# channel.net
KiCad netlist of a schematic drawn in Altium Designer
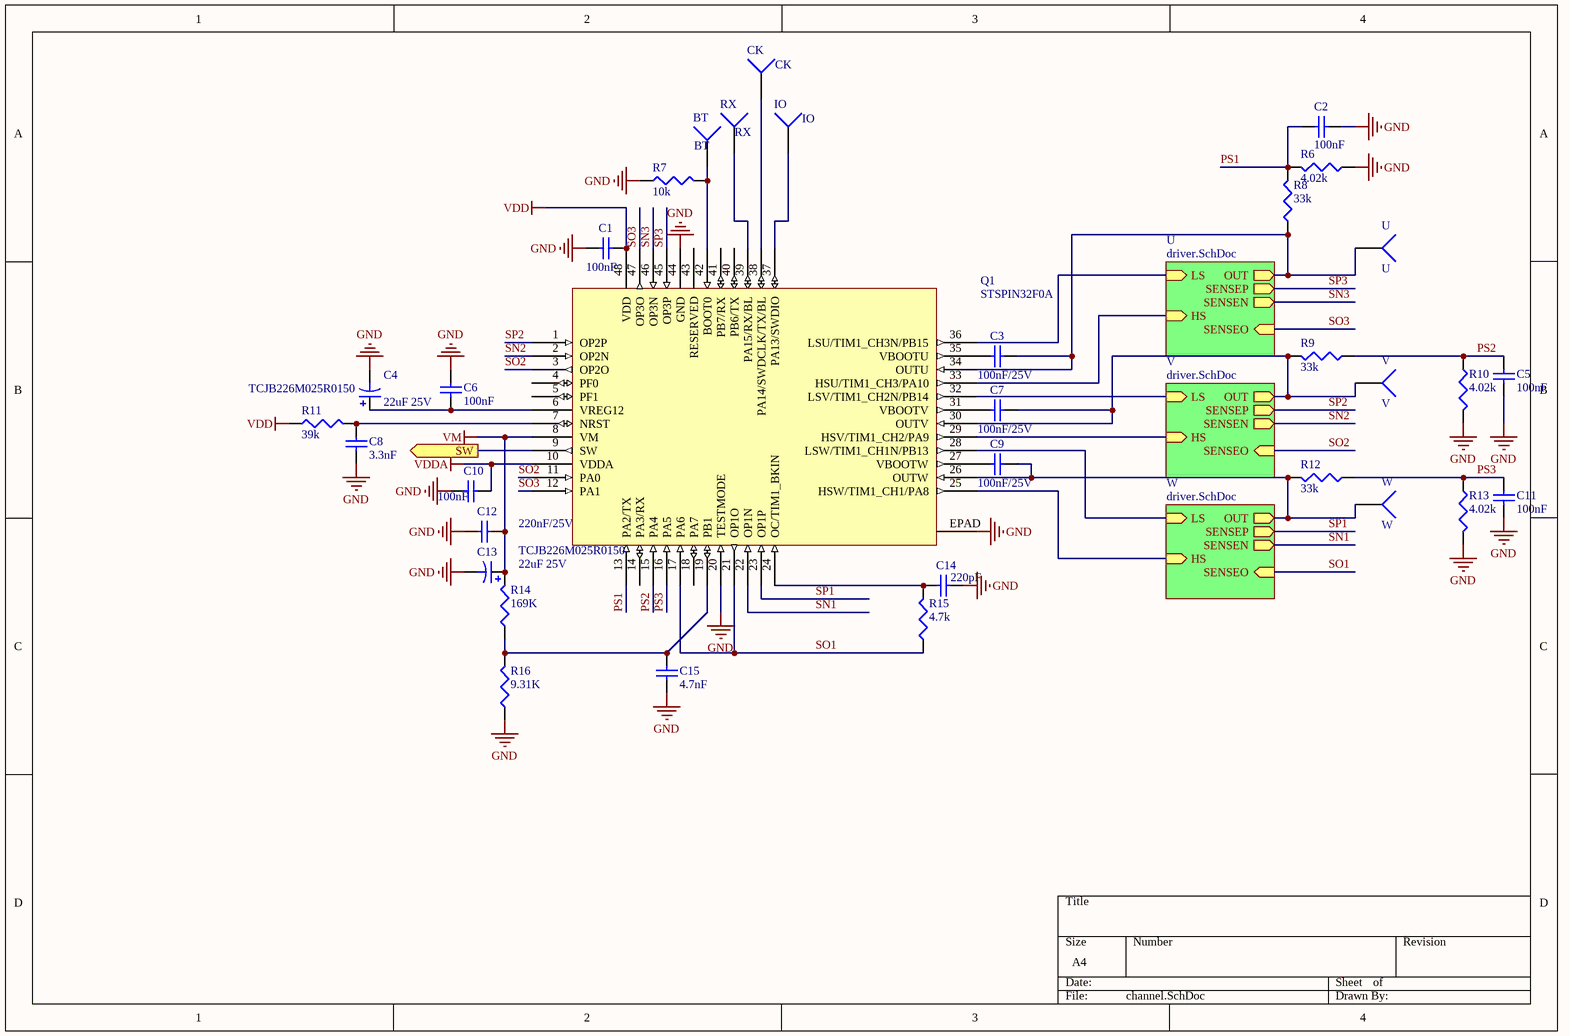
[diagram p0: channel.SchDoc]

(export (version "E")
  (design (tool "Eeschema 10.0.6"))
  (components
    (comp (ref "BT")
      (value "BT")
      (footprint "solder_pin_small")
      (description "Socket")
      (fields (field (name "PUBLISHER") "Altium Limited"))
      (libsource (lib "Miscellaneous Connectors") (part "Socket"))
    )
    (comp (ref "C1")
      (value "100nF")
      (description "Capacitor")
      (fields (field (name "PUBLISHER") "Altium Limited"))
      (libsource (lib "Miscellaneous Devices") (part "Cap"))
    )
    (comp (ref "C2")
      (value "100nF")
      (description "Capacitor")
      (fields (field (name "PUBLISHER") "Altium Limited"))
      (libsource (lib "Miscellaneous Devices") (part "Cap"))
    )
    (comp (ref "C3")
      (value "100nF/25V")
      (description "Capacitor")
      (fields (field (name "PUBLISHER") "Altium Limited"))
      (libsource (lib "Miscellaneous Devices") (part "Cap"))
    )
    (comp (ref "C4")
      (value "TCJB226M025R0150")
      (footprint "my_1210_pol")
      (description "Polarized Capacitor (Surface Mount)")
      (fields (field (name "ALTIUM_VALUE") "22uF 25V") (field (name "PUBLISHER") "Altium Limited"))
      (libsource (lib "Miscellaneous Devices") (part "Cap Pol3"))
    )
    (comp (ref "C5")
      (value "100nF")
      (description "Capacitor")
      (fields (field (name "PUBLISHER") "Altium Limited"))
      (libsource (lib "Miscellaneous Devices") (part "Cap"))
    )
    (comp (ref "C6")
      (value "100nF")
      (description "Capacitor")
      (fields (field (name "PUBLISHER") "Altium Limited"))
      (libsource (lib "Miscellaneous Devices") (part "Cap"))
    )
    (comp (ref "C7")
      (value "100nF/25V")
      (description "Capacitor")
      (fields (field (name "PUBLISHER") "Altium Limited"))
      (libsource (lib "Miscellaneous Devices") (part "Cap"))
    )
    (comp (ref "C8")
      (value "3.3nF")
      (description "Capacitor")
      (fields (field (name "PUBLISHER") "Altium Limited"))
      (libsource (lib "Miscellaneous Devices") (part "Cap"))
    )
    (comp (ref "C9")
      (value "100nF/25V")
      (description "Capacitor")
      (fields (field (name "PUBLISHER") "Altium Limited"))
      (libsource (lib "Miscellaneous Devices") (part "Cap"))
    )
    (comp (ref "C10")
      (value "100nF")
      (description "Capacitor")
      (fields (field (name "PUBLISHER") "Altium Limited"))
      (libsource (lib "Miscellaneous Devices") (part "Cap"))
    )
    (comp (ref "C11")
      (value "100nF")
      (description "Capacitor")
      (fields (field (name "PUBLISHER") "Altium Limited"))
      (libsource (lib "Miscellaneous Devices") (part "Cap"))
    )
    (comp (ref "C12")
      (value "220nF/25V")
      (description "Capacitor")
      (fields (field (name "PUBLISHER") "Altium Limited"))
      (libsource (lib "Miscellaneous Devices") (part "Cap"))
    )
    (comp (ref "C13")
      (value "TCJB226M025R0150")
      (footprint "my_1210_pol")
      (description "Polarized Capacitor (Surface Mount)")
      (fields (field (name "ALTIUM_VALUE") "22uF 25V") (field (name "PUBLISHER") "Altium Limited"))
      (libsource (lib "Miscellaneous Devices") (part "Cap Pol3"))
    )
    (comp (ref "C14")
      (value "220pF")
      (description "Capacitor")
      (fields (field (name "PUBLISHER") "Altium Limited"))
      (libsource (lib "Miscellaneous Devices") (part "Cap"))
    )
    (comp (ref "C15")
      (value "4.7nF")
      (description "Capacitor")
      (fields (field (name "PUBLISHER") "Altium Limited"))
      (libsource (lib "Miscellaneous Devices") (part "Cap"))
    )
    (comp (ref "CK")
      (value "CK")
      (footprint "solder_pin_small")
      (description "Socket")
      (fields (field (name "PUBLISHER") "Altium Limited"))
      (libsource (lib "Miscellaneous Connectors") (part "Socket"))
    )
    (comp (ref "IO")
      (value "IO")
      (footprint "solder_pin_small")
      (description "Socket")
      (fields (field (name "PUBLISHER") "Altium Limited"))
      (libsource (lib "Miscellaneous Connectors") (part "Socket"))
    )
    (comp (ref "Q1")
      (value "STSPIN32F0A")
      (footprint "VFQFPN48")
      (libsource (lib "components") (part "STSPIN32F0A"))
    )
    (comp (ref "R6")
      (value "4.02k")
      (description "Resistor")
      (fields (field (name "PUBLISHER") "Altium Limited"))
      (libsource (lib "Miscellaneous Devices") (part "Res3"))
    )
    (comp (ref "R7")
      (value "10k")
      (description "Resistor")
      (fields (field (name "PUBLISHER") "Altium Limited"))
      (libsource (lib "Miscellaneous Devices") (part "Res3"))
    )
    (comp (ref "R8")
      (value "33k")
      (description "Resistor")
      (fields (field (name "PUBLISHER") "Altium Limited"))
      (libsource (lib "Miscellaneous Devices") (part "Res3"))
    )
    (comp (ref "R9")
      (value "33k")
      (description "Resistor")
      (fields (field (name "PUBLISHER") "Altium Limited"))
      (libsource (lib "Miscellaneous Devices") (part "Res3"))
    )
    (comp (ref "R10")
      (value "4.02k")
      (description "Resistor")
      (fields (field (name "PUBLISHER") "Altium Limited"))
      (libsource (lib "Miscellaneous Devices") (part "Res3"))
    )
    (comp (ref "R11")
      (value "39k")
      (description "Resistor")
      (fields (field (name "PUBLISHER") "Altium Limited"))
      (libsource (lib "Miscellaneous Devices") (part "Res3"))
    )
    (comp (ref "R12")
      (value "33k")
      (description "Resistor")
      (fields (field (name "PUBLISHER") "Altium Limited"))
      (libsource (lib "Miscellaneous Devices") (part "Res3"))
    )
    (comp (ref "R13")
      (value "4.02k")
      (description "Resistor")
      (fields (field (name "PUBLISHER") "Altium Limited"))
      (libsource (lib "Miscellaneous Devices") (part "Res3"))
    )
    (comp (ref "R14")
      (value "169K")
      (description "Resistor")
      (fields (field (name "PUBLISHER") "Altium Limited"))
      (libsource (lib "Miscellaneous Devices") (part "Res3"))
    )
    (comp (ref "R15")
      (value "4.7k")
      (description "Resistor")
      (fields (field (name "PUBLISHER") "Altium Limited"))
      (libsource (lib "Miscellaneous Devices") (part "Res3"))
    )
    (comp (ref "R16")
      (value "9.31K")
      (description "Resistor")
      (fields (field (name "PUBLISHER") "Altium Limited"))
      (libsource (lib "Miscellaneous Devices") (part "Res3"))
    )
    (comp (ref "RX")
      (value "RX")
      (footprint "solder_pin_small")
      (description "Socket")
      (fields (field (name "PUBLISHER") "Altium Limited"))
      (libsource (lib "Miscellaneous Connectors") (part "Socket"))
    )
    (comp (ref "U")
      (value "U")
      (footprint "solder_pin_small")
      (description "Socket")
      (fields (field (name "PUBLISHER") "Altium Limited"))
      (libsource (lib "Miscellaneous Connectors") (part "Socket"))
    )
    (comp (ref "V")
      (value "V")
      (footprint "solder_pin_small")
      (description "Socket")
      (fields (field (name "PUBLISHER") "Altium Limited"))
      (libsource (lib "Miscellaneous Connectors") (part "Socket"))
    )
    (comp (ref "W")
      (value "W")
      (footprint "solder_pin_small")
      (description "Socket")
      (fields (field (name "PUBLISHER") "Altium Limited"))
      (libsource (lib "Miscellaneous Connectors") (part "Socket"))
    )
  )
  (nets
    (net (code "1") (name "/HS") (class "Default")
      (node (ref "Q1") (pin "25") (pinfunction "HSW/TIM1_CH1/PA8_25") (pintype "output"))
    )
    (net (code "2") (name "/HS_1") (class "Default")
      (node (ref "Q1") (pin "33") (pinfunction "HSU/TIM1_CH3/PA10_33") (pintype "output"))
    )
    (net (code "3") (name "/HS_2") (class "Default")
      (node (ref "Q1") (pin "29") (pinfunction "HSV/TIM1_CH2/PA9_29") (pintype "output"))
    )
    (net (code "4") (name "/LS") (class "Default")
      (node (ref "Q1") (pin "36") (pinfunction "LSU/TIM1_CH3N/PB15_36") (pintype "output"))
    )
    (net (code "5") (name "/LS_1") (class "Default")
      (node (ref "Q1") (pin "32") (pinfunction "LSV/TIM1_CH2N/PB14_32") (pintype "output"))
    )
    (net (code "6") (name "/LS_2") (class "Default")
      (node (ref "Q1") (pin "28") (pinfunction "LSW/TIM1_CH1N/PB13_28") (pintype "output"))
    )
    (net (code "7") (name "/OUT") (class "Default")
      (node (ref "C9") (pin "2") (pinfunction "2_2") (pintype "passive"))
      (node (ref "Q1") (pin "26") (pinfunction "OUTW_26") (pintype "input"))
      (node (ref "R12") (pin "2") (pinfunction "2_2") (pintype "passive"))
      (node (ref "W") (pin "1") (pinfunction "1_1") (pintype "passive"))
    )
    (net (code "8") (name "/OUT_1") (class "Default")
      (node (ref "C3") (pin "2") (pinfunction "2_2") (pintype "passive"))
      (node (ref "Q1") (pin "34") (pinfunction "OUTU_34") (pintype "input"))
      (node (ref "R8") (pin "1") (pinfunction "1_1") (pintype "passive"))
      (node (ref "U") (pin "1") (pinfunction "1_1") (pintype "passive"))
    )
    (net (code "9") (name "/OUT_2") (class "Default")
      (node (ref "C7") (pin "2") (pinfunction "2_2") (pintype "passive"))
      (node (ref "Q1") (pin "30") (pinfunction "OUTV_30") (pintype "input"))
      (node (ref "R9") (pin "2") (pinfunction "2_2") (pintype "passive"))
      (node (ref "V") (pin "1") (pinfunction "1_1") (pintype "passive"))
    )
    (net (code "10") (name "/PS1") (class "Default")
      (node (ref "C2") (pin "1") (pinfunction "1_1") (pintype "passive"))
      (node (ref "Q1") (pin "13") (pinfunction "PA2/TX_13") (pintype "input"))
      (node (ref "R6") (pin "2") (pinfunction "2_2") (pintype "passive"))
      (node (ref "R8") (pin "2") (pinfunction "2_2") (pintype "passive"))
    )
    (net (code "11") (name "/PS2") (class "Default")
      (node (ref "C5") (pin "2") (pinfunction "2_2") (pintype "passive"))
      (node (ref "Q1") (pin "15") (pinfunction "PA4_15") (pintype "input"))
      (node (ref "R10") (pin "1") (pinfunction "1_1") (pintype "passive"))
      (node (ref "R9") (pin "1") (pinfunction "1_1") (pintype "passive"))
    )
    (net (code "12") (name "/PS3") (class "Default")
      (node (ref "C11") (pin "2") (pinfunction "2_2") (pintype "passive"))
      (node (ref "Q1") (pin "16") (pinfunction "PA5_16") (pintype "input"))
      (node (ref "R12") (pin "1") (pinfunction "1_1") (pintype "passive"))
      (node (ref "R13") (pin "1") (pinfunction "1_1") (pintype "passive"))
    )
    (net (code "13") (name "/SN1") (class "Default")
      (node (ref "Q1") (pin "22") (pinfunction "OP1N_22") (pintype "input"))
    )
    (net (code "14") (name "/SN2") (class "Default")
      (node (ref "Q1") (pin "2") (pinfunction "OP2N_2") (pintype "input"))
    )
    (net (code "15") (name "/SN3") (class "Default")
      (node (ref "Q1") (pin "46") (pinfunction "OP3N_46") (pintype "input"))
    )
    (net (code "16") (name "/SO1") (class "Default")
      (node (ref "Q1") (pin "17") (pinfunction "PA6_17") (pintype "input"))
      (node (ref "Q1") (pin "21") (pinfunction "OP1O_21") (pintype "output"))
      (node (ref "R15") (pin "1") (pinfunction "1_1") (pintype "passive"))
    )
    (net (code "17") (name "/SO2") (class "Default")
      (node (ref "Q1") (pin "11") (pinfunction "PA0_11") (pintype "input"))
      (node (ref "Q1") (pin "3") (pinfunction "OP2O_3") (pintype "output"))
    )
    (net (code "18") (name "/SO3") (class "Default")
      (node (ref "Q1") (pin "12") (pinfunction "PA1_12") (pintype "input"))
      (node (ref "Q1") (pin "47") (pinfunction "OP3O_47") (pintype "output"))
    )
    (net (code "19") (name "/SP1") (class "Default")
      (node (ref "Q1") (pin "23") (pinfunction "OP1P_23") (pintype "input"))
    )
    (net (code "20") (name "/SP2") (class "Default")
      (node (ref "Q1") (pin "1") (pinfunction "OP2P_1") (pintype "input"))
    )
    (net (code "21") (name "/SP3") (class "Default")
      (node (ref "Q1") (pin "45") (pinfunction "OP3P_45") (pintype "input"))
    )
    (net (code "22") (name "/SW") (class "Default")
      (node (ref "Q1") (pin "9") (pinfunction "SW_9") (pintype "output"))
    )
    (net (code "23") (name "GND") (class "Default")
      (node (ref "C1") (pin "1") (pinfunction "1_1") (pintype "passive"))
      (node (ref "C10") (pin "2") (pinfunction "2_2") (pintype "passive"))
      (node (ref "C11") (pin "1") (pinfunction "1_1") (pintype "passive"))
      (node (ref "C12") (pin "2") (pinfunction "2_2") (pintype "passive"))
      (node (ref "C13") (pin "2") (pinfunction "2_2") (pintype "passive"))
      (node (ref "C14") (pin "2") (pinfunction "2_2") (pintype "passive"))
      (node (ref "C15") (pin "2") (pinfunction "2_2") (pintype "passive"))
      (node (ref "C2") (pin "2") (pinfunction "2_2") (pintype "passive"))
      (node (ref "C4") (pin "2") (pinfunction "2_2") (pintype "passive"))
      (node (ref "C5") (pin "1") (pinfunction "1_1") (pintype "passive"))
      (node (ref "C6") (pin "1") (pinfunction "1_1") (pintype "passive"))
      (node (ref "C8") (pin "2") (pinfunction "2_2") (pintype "passive"))
      (node (ref "Q1") (pin "20") (pinfunction "TESTMODE_20") (pintype "input"))
      (node (ref "Q1") (pin "44") (pinfunction "GND_44") (pintype "power_in"))
      (node (ref "Q1") (pin "EPAD") (pinfunction "EPAD_EPAD") (pintype "power_in"))
      (node (ref "R10") (pin "2") (pinfunction "2_2") (pintype "passive"))
      (node (ref "R13") (pin "2") (pinfunction "2_2") (pintype "passive"))
      (node (ref "R16") (pin "1") (pinfunction "1_1") (pintype "passive"))
      (node (ref "R6") (pin "1") (pinfunction "1_1") (pintype "passive"))
      (node (ref "R7") (pin "1") (pinfunction "1_1") (pintype "passive"))
    )
    (net (code "24") (name "Net-(Q1-BOOT0)") (class "Default")
      (node (ref "BT") (pin "1") (pinfunction "1_1") (pintype "passive"))
      (node (ref "Q1") (pin "42") (pinfunction "BOOT0_42") (pintype "input"))
      (node (ref "R7") (pin "2") (pinfunction "2_2") (pintype "passive"))
    )
    (net (code "25") (name "Net-(Q1-NRST)") (class "Default")
      (node (ref "C8") (pin "1") (pinfunction "1_1") (pintype "passive"))
      (node (ref "Q1") (pin "7") (pinfunction "NRST_7") (pintype "bidirectional"))
      (node (ref "R11") (pin "2") (pinfunction "2_2") (pintype "passive"))
    )
    (net (code "26") (name "Net-(Q1-OC{slash}TIM1_BKIN)") (class "Default")
      (node (ref "C14") (pin "1") (pinfunction "1_1") (pintype "passive"))
      (node (ref "Q1") (pin "24") (pinfunction "OC/TIM1_BKIN_24") (pintype "input"))
      (node (ref "R15") (pin "2") (pinfunction "2_2") (pintype "passive"))
    )
    (net (code "27") (name "Net-(Q1-PA13{slash}SWDIO)") (class "Default")
      (node (ref "IO") (pin "1") (pinfunction "1_1") (pintype "passive"))
      (node (ref "Q1") (pin "37") (pinfunction "PA13/SWDIO_37") (pintype "bidirectional"))
    )
    (net (code "28") (name "Net-(Q1-PA14{slash}SWDCLK{slash}TX{slash}BL)") (class "Default")
      (node (ref "CK") (pin "1") (pinfunction "1_1") (pintype "passive"))
      (node (ref "Q1") (pin "38") (pinfunction "PA14/SWDCLK/TX/BL_38") (pintype "bidirectional"))
    )
    (net (code "29") (name "Net-(Q1-PA15{slash}RX{slash}BL)") (class "Default")
      (node (ref "Q1") (pin "39") (pinfunction "PA15/RX/BL_39") (pintype "bidirectional"))
      (node (ref "RX") (pin "1") (pinfunction "1_1") (pintype "passive"))
    )
    (net (code "30") (name "Net-(Q1-PB1)") (class "Default")
      (node (ref "C15") (pin "1") (pinfunction "1_1") (pintype "passive"))
      (node (ref "Q1") (pin "19") (pinfunction "PB1_19") (pintype "bidirectional"))
      (node (ref "R14") (pin "1") (pinfunction "1_1") (pintype "passive"))
      (node (ref "R16") (pin "2") (pinfunction "2_2") (pintype "passive"))
    )
    (net (code "31") (name "Net-(Q1-VBOOTU)") (class "Default")
      (node (ref "C3") (pin "1") (pinfunction "1_1") (pintype "passive"))
      (node (ref "Q1") (pin "35") (pinfunction "VBOOTU_35") (pintype "output"))
    )
    (net (code "32") (name "Net-(Q1-VBOOTV)") (class "Default")
      (node (ref "C7") (pin "1") (pinfunction "1_1") (pintype "passive"))
      (node (ref "Q1") (pin "31") (pinfunction "VBOOTV_31") (pintype "output"))
    )
    (net (code "33") (name "Net-(Q1-VBOOTW)") (class "Default")
      (node (ref "C9") (pin "1") (pinfunction "1_1") (pintype "passive"))
      (node (ref "Q1") (pin "27") (pinfunction "VBOOTW_27") (pintype "output"))
    )
    (net (code "34") (name "Net-(Q1-VREG12)") (class "Default")
      (node (ref "C4") (pin "1") (pinfunction "1_1") (pintype "passive"))
      (node (ref "C6") (pin "2") (pinfunction "2_2") (pintype "passive"))
      (node (ref "Q1") (pin "6") (pinfunction "VREG12_6") (pintype "power_in"))
    )
    (net (code "35") (name "VDD") (class "Default")
      (node (ref "C1") (pin "2") (pinfunction "2_2") (pintype "passive"))
      (node (ref "Q1") (pin "48") (pinfunction "VDD_48") (pintype "power_in"))
      (node (ref "R11") (pin "1") (pinfunction "1_1") (pintype "passive"))
    )
    (net (code "36") (name "VDDA") (class "Default")
      (node (ref "C10") (pin "1") (pinfunction "1_1") (pintype "passive"))
      (node (ref "Q1") (pin "10") (pinfunction "VDDA_10") (pintype "power_in"))
    )
    (net (code "37") (name "VM") (class "Default")
      (node (ref "C12") (pin "1") (pinfunction "1_1") (pintype "passive"))
      (node (ref "C13") (pin "1") (pinfunction "1_1") (pintype "passive"))
      (node (ref "Q1") (pin "8") (pinfunction "VM_8") (pintype "power_in"))
      (node (ref "R14") (pin "2") (pinfunction "2_2") (pintype "passive"))
    )
    (net (code "38") (name "unconnected-(Q1-PA3{slash}RX-Pad14)") (class "Default")
      (node (ref "Q1") (pin "14") (pinfunction "PA3/RX_14") (pintype "bidirectional"))
    )
    (net (code "39") (name "unconnected-(Q1-PA7-Pad18)") (class "Default")
      (node (ref "Q1") (pin "18") (pinfunction "PA7_18") (pintype "bidirectional"))
    )
    (net (code "40") (name "unconnected-(Q1-PB6{slash}TX-Pad40)") (class "Default")
      (node (ref "Q1") (pin "40") (pinfunction "PB6/TX_40") (pintype "bidirectional"))
    )
    (net (code "41") (name "unconnected-(Q1-PB7{slash}RX-Pad41)") (class "Default")
      (node (ref "Q1") (pin "41") (pinfunction "PB7/RX_41") (pintype "bidirectional"))
    )
    (net (code "42") (name "unconnected-(Q1-PF0-Pad4)") (class "Default")
      (node (ref "Q1") (pin "4") (pinfunction "PF0_4") (pintype "bidirectional"))
    )
    (net (code "43") (name "unconnected-(Q1-PF1-Pad5)") (class "Default")
      (node (ref "Q1") (pin "5") (pinfunction "PF1_5") (pintype "bidirectional"))
    )
    (net (code "44") (name "unconnected-(Q1-RESERVED-Pad43)") (class "Default")
      (node (ref "Q1") (pin "43") (pinfunction "RESERVED_43") (pintype "passive"))
    )
  )
)
